# mezzanine.net
KiCad netlist of a schematic drawn in Altium Designer
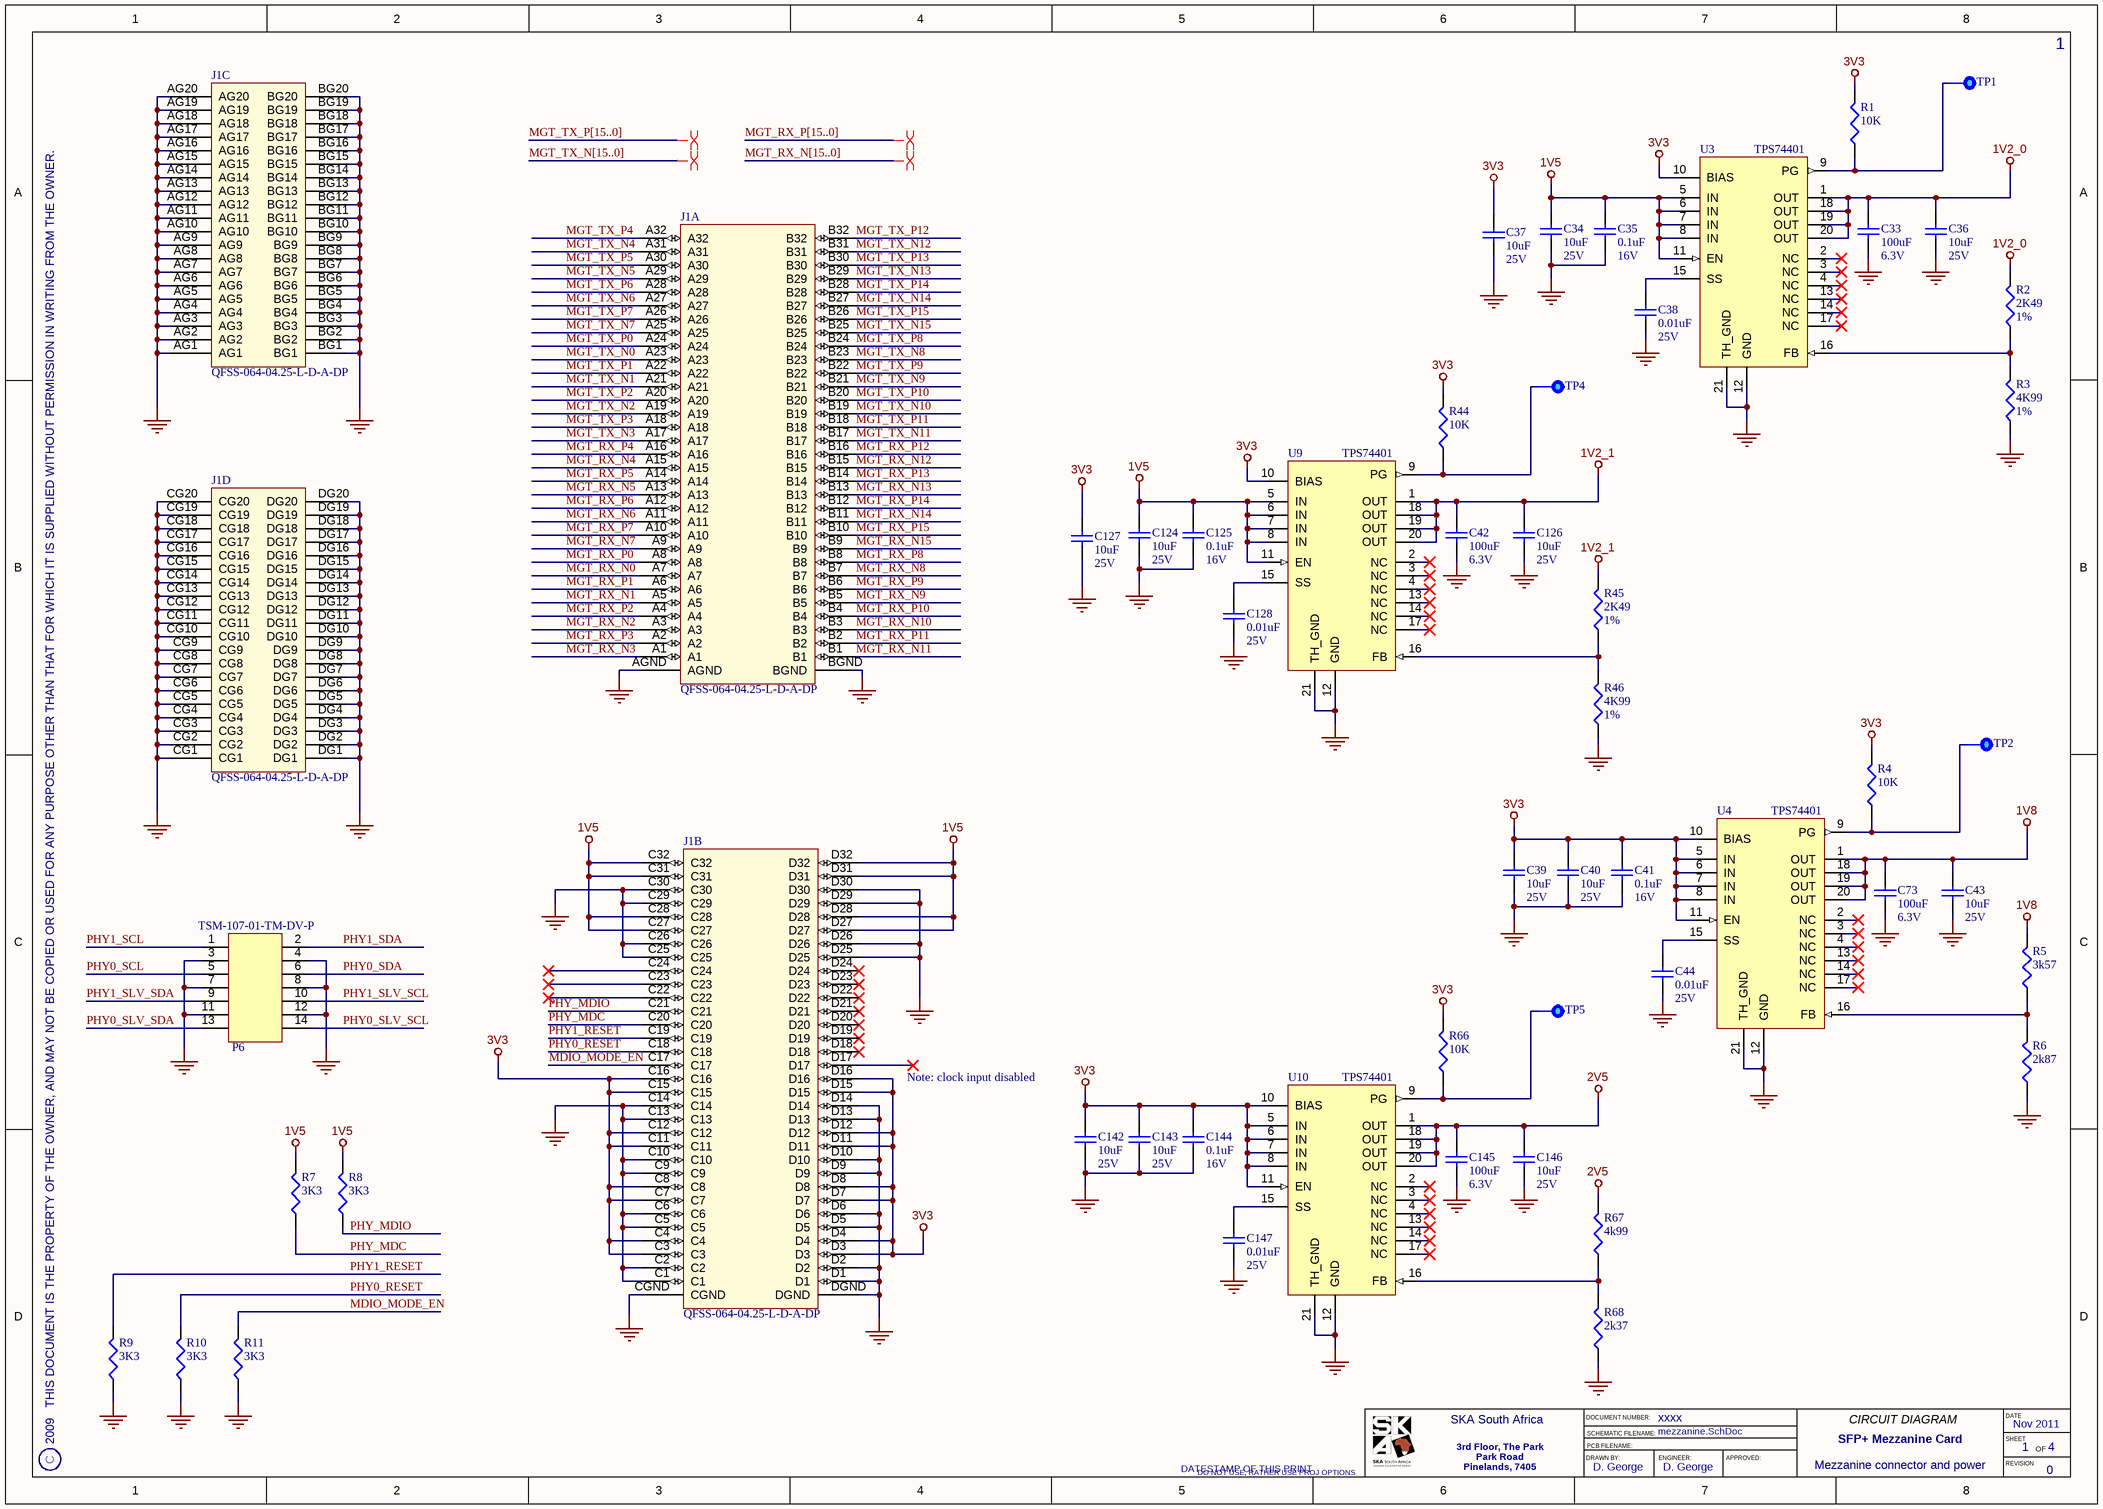
[diagram p0: mezzanine.SchDoc]

(export (version "E")
  (design (tool "Eeschema 10.0.6"))
  (components
    (comp (ref "C33")
      (value "100uF")
      (footprint "CAPC3225X270L")
      (description "100uF, 1210, Ceramic Capacitor")
      (fields
        (field (name "RATING") "6.3V")
        (field (name "MANUFACTURER") "TDK")
        (field (name "PARTNUM") "C3225X5R0J107M")
      )
      (libsource (lib "altium_db") (part "CapStd"))
    )
    (comp (ref "C34")
      (value "10uF")
      (footprint "CAPC3225X200L")
      (description "10uF, Ceramic Capacitor")
      (fields
        (field (name "RATING") "25V")
        (field (name "MANUFACTURER") "MURATA")
        (field (name "PARTNUM") "GRM32DR61E106KA12L")
      )
      (libsource (lib "altium_db") (part "CapStd"))
    )
    (comp (ref "C35")
      (value "0.1uF")
      (footprint "CAPC1005X60L")
      (description "0.1uF, Ceramic Capacitor")
      (fields
        (field (name "RATING") "16V")
        (field (name "MANUFACTURER") "VENKEL")
        (field (name "PARTNUM") "C0402X7R160-104KN")
      )
      (libsource (lib "altium_db") (part "CapStd"))
    )
    (comp (ref "C36")
      (value "10uF")
      (footprint "CAPC3225X200L")
      (description "10uF, Ceramic Capacitor")
      (fields
        (field (name "RATING") "25V")
        (field (name "MANUFACTURER") "MURATA")
        (field (name "PARTNUM") "GRM32DR61E106KA12L")
      )
      (libsource (lib "altium_db") (part "CapStd"))
    )
    (comp (ref "C37")
      (value "10uF")
      (footprint "CAPC3225X200L")
      (description "10uF, Ceramic Capacitor")
      (fields
        (field (name "RATING") "25V")
        (field (name "MANUFACTURER") "MURATA")
        (field (name "PARTNUM") "GRM32DR61E106KA12L")
      )
      (libsource (lib "altium_db") (part "CapStd"))
    )
    (comp (ref "C38")
      (value "0.01uF")
      (footprint "CAPC1005X55L")
      (description "0.01uF, Ceramic Capacitor")
      (fields
        (field (name "RATING") "25V")
        (field (name "MANUFACTURER") "MURATA")
        (field (name "PARTNUM") "GRM155R71E103KA01D")
      )
      (libsource (lib "altium_db") (part "CapStd"))
    )
    (comp (ref "C39")
      (value "10uF")
      (footprint "CAPC3225X200L")
      (description "10uF, Ceramic Capacitor")
      (fields
        (field (name "RATING") "25V")
        (field (name "MANUFACTURER") "MURATA")
        (field (name "PARTNUM") "GRM32DR61E106KA12L")
      )
      (libsource (lib "altium_db") (part "CapStd"))
    )
    (comp (ref "C40")
      (value "10uF")
      (footprint "CAPC3225X200L")
      (description "10uF, Ceramic Capacitor")
      (fields
        (field (name "RATING") "25V")
        (field (name "MANUFACTURER") "MURATA")
        (field (name "PARTNUM") "GRM32DR61E106KA12L")
      )
      (libsource (lib "altium_db") (part "CapStd"))
    )
    (comp (ref "C41")
      (value "0.1uF")
      (footprint "CAPC1005X60L")
      (description "0.1uF, Ceramic Capacitor")
      (fields
        (field (name "RATING") "16V")
        (field (name "MANUFACTURER") "VENKEL")
        (field (name "PARTNUM") "C0402X7R160-104KN")
      )
      (libsource (lib "altium_db") (part "CapStd"))
    )
    (comp (ref "C42")
      (value "100uF")
      (footprint "CAPC3225X270L")
      (description "100uF, 1210, Ceramic Capacitor")
      (fields
        (field (name "RATING") "6.3V")
        (field (name "MANUFACTURER") "TDK")
        (field (name "PARTNUM") "C3225X5R0J107M")
      )
      (libsource (lib "altium_db") (part "CapStd"))
    )
    (comp (ref "C43")
      (value "10uF")
      (footprint "CAPC3225X200L")
      (description "10uF, Ceramic Capacitor")
      (fields
        (field (name "RATING") "25V")
        (field (name "MANUFACTURER") "MURATA")
        (field (name "PARTNUM") "GRM32DR61E106KA12L")
      )
      (libsource (lib "altium_db") (part "CapStd"))
    )
    (comp (ref "C44")
      (value "0.01uF")
      (footprint "CAPC1005X55L")
      (description "0.01uF, Ceramic Capacitor")
      (fields
        (field (name "RATING") "25V")
        (field (name "MANUFACTURER") "MURATA")
        (field (name "PARTNUM") "GRM155R71E103KA01D")
      )
      (libsource (lib "altium_db") (part "CapStd"))
    )
    (comp (ref "C73")
      (value "100uF")
      (footprint "CAPC3225X270L")
      (description "100uF, 1210, Ceramic Capacitor")
      (fields
        (field (name "RATING") "6.3V")
        (field (name "MANUFACTURER") "TDK")
        (field (name "PARTNUM") "C3225X5R0J107M")
      )
      (libsource (lib "altium_db") (part "CapStd"))
    )
    (comp (ref "C124")
      (value "10uF")
      (footprint "CAPC3225X200L")
      (description "10uF, Ceramic Capacitor")
      (fields
        (field (name "RATING") "25V")
        (field (name "MANUFACTURER") "MURATA")
        (field (name "PARTNUM") "GRM32DR61E106KA12L")
      )
      (libsource (lib "altium_db") (part "CapStd"))
    )
    (comp (ref "C125")
      (value "0.1uF")
      (footprint "CAPC1005X60L")
      (description "0.1uF, Ceramic Capacitor")
      (fields
        (field (name "RATING") "16V")
        (field (name "MANUFACTURER") "VENKEL")
        (field (name "PARTNUM") "C0402X7R160-104KN")
      )
      (libsource (lib "altium_db") (part "CapStd"))
    )
    (comp (ref "C126")
      (value "10uF")
      (footprint "CAPC3225X200L")
      (description "10uF, Ceramic Capacitor")
      (fields
        (field (name "RATING") "25V")
        (field (name "MANUFACTURER") "MURATA")
        (field (name "PARTNUM") "GRM32DR61E106KA12L")
      )
      (libsource (lib "altium_db") (part "CapStd"))
    )
    (comp (ref "C127")
      (value "10uF")
      (footprint "CAPC3225X200L")
      (description "10uF, Ceramic Capacitor")
      (fields
        (field (name "RATING") "25V")
        (field (name "MANUFACTURER") "MURATA")
        (field (name "PARTNUM") "GRM32DR61E106KA12L")
      )
      (libsource (lib "altium_db") (part "CapStd"))
    )
    (comp (ref "C128")
      (value "0.01uF")
      (footprint "CAPC1005X55L")
      (description "0.01uF, Ceramic Capacitor")
      (fields
        (field (name "RATING") "25V")
        (field (name "MANUFACTURER") "MURATA")
        (field (name "PARTNUM") "GRM155R71E103KA01D")
      )
      (libsource (lib "altium_db") (part "CapStd"))
    )
    (comp (ref "C142")
      (value "10uF")
      (footprint "CAPC3225X200L")
      (description "10uF, Ceramic Capacitor")
      (fields
        (field (name "RATING") "25V")
        (field (name "MANUFACTURER") "MURATA")
        (field (name "PARTNUM") "GRM32DR61E106KA12L")
      )
      (libsource (lib "altium_db") (part "CapStd"))
    )
    (comp (ref "C143")
      (value "10uF")
      (footprint "CAPC3225X200L")
      (description "10uF, Ceramic Capacitor")
      (fields
        (field (name "RATING") "25V")
        (field (name "MANUFACTURER") "MURATA")
        (field (name "PARTNUM") "GRM32DR61E106KA12L")
      )
      (libsource (lib "altium_db") (part "CapStd"))
    )
    (comp (ref "C144")
      (value "0.1uF")
      (footprint "CAPC1005X60L")
      (description "0.1uF, Ceramic Capacitor")
      (fields
        (field (name "RATING") "16V")
        (field (name "MANUFACTURER") "VENKEL")
        (field (name "PARTNUM") "C0402X7R160-104KN")
      )
      (libsource (lib "altium_db") (part "CapStd"))
    )
    (comp (ref "C145")
      (value "100uF")
      (footprint "CAPC3225X270L")
      (description "100uF, 1210, Ceramic Capacitor")
      (fields
        (field (name "RATING") "6.3V")
        (field (name "MANUFACTURER") "TDK")
        (field (name "PARTNUM") "C3225X5R0J107M")
      )
      (libsource (lib "altium_db") (part "CapStd"))
    )
    (comp (ref "C146")
      (value "10uF")
      (footprint "CAPC3225X200L")
      (description "10uF, Ceramic Capacitor")
      (fields
        (field (name "RATING") "25V")
        (field (name "MANUFACTURER") "MURATA")
        (field (name "PARTNUM") "GRM32DR61E106KA12L")
      )
      (libsource (lib "altium_db") (part "CapStd"))
    )
    (comp (ref "C147")
      (value "0.01uF")
      (footprint "CAPC1005X55L")
      (description "0.01uF, Ceramic Capacitor")
      (fields
        (field (name "RATING") "25V")
        (field (name "MANUFACTURER") "MURATA")
        (field (name "PARTNUM") "GRM155R71E103KA01D")
      )
      (libsource (lib "altium_db") (part "CapStd"))
    )
    (comp (ref "J1")
      (value "QFSS-064-04.25-L-D-A-DP")
      (footprint "SAMTEC_QFSS-064-04.25-L-D-DP-A")
      (description "Shielded, 64-Differential Pair, Rugged High-Speed Terminal Strip, 0.635mm Pitch")
      (fields (field (name "PARTNUM") "QFSS-064-04.25-L-D-A-DP") (field (name "MANUFACTURER") "SAMTEC"))
      (libsource (lib "") (part "QFSS-064-04.25-L-D-A-DP_1"))
    )
    (comp (ref "P6")
      (value "TSM-107-01-TM-DV-P")
      (footprint "SAMTEC_TSM-107-01-TM-DV-P")
      (description "2x7, 2.54 mm Pitch, Male Header")
      (fields (field (name "PARTNUM") "TSM-107-01-TM-DV-P") (field (name "MANUFACTURER") "SAMTEC"))
      (libsource (lib "altium_db") (part "con_hdr_2x7"))
    )
    (comp (ref "R1")
      (value "10K")
      (footprint "RESC1005X40L")
      (description "10K, 1.1mm x 0.5mm, Thick Film Resistor")
      (fields (field (name "MANUFACTURER") "ROYALOHM") (field (name "PARTNUM") "0402WGJ0103T1E"))
      (libsource (lib "altium_db") (part "ResStd"))
    )
    (comp (ref "R2")
      (value "2K49")
      (footprint "RESC1005X40L")
      (description "2K49, 1.1mm x 0.5mm, Thick Film Resistor")
      (fields
        (field (name "MANUFACTURER") "ROYALOHM")
        (field (name "PARTNUM") "0402WGF2K49T1E")
        (field (name "TOLERANCE") "1%")
      )
      (libsource (lib "altium_db") (part "ResStd"))
    )
    (comp (ref "R3")
      (value "4K99")
      (footprint "RESC1005X40L")
      (description "4K99, 1.1mm x 0.5mm, Thick Film Resistor")
      (fields
        (field (name "MANUFACTURER") "ROYALOHM")
        (field (name "PARTNUM") "0402WGF4991T1E")
        (field (name "TOLERANCE") "1%")
      )
      (libsource (lib "altium_db") (part "ResStd"))
    )
    (comp (ref "R4")
      (value "10K")
      (footprint "RESC1005X40L")
      (description "10K, 1.1mm x 0.5mm, Thick Film Resistor")
      (fields (field (name "MANUFACTURER") "ROYALOHM") (field (name "PARTNUM") "0402WGJ0103T1E"))
      (libsource (lib "altium_db") (part "ResStd"))
    )
    (comp (ref "R5")
      (value "3k57")
      (footprint "RESC1005X40L")
      (description "3K57, 1.1mm x 0.5mm, Thick Film Resistor")
      (fields (field (name "MANUFACTURER") "STACKPOLE") (field (name "PARTNUM") "RMC0402FT3K57"))
      (libsource (lib "altium_db") (part "ResStd"))
    )
    (comp (ref "R6")
      (value "2k87")
      (footprint "RESC1005X40L")
      (description "2K87, 1.1mm x 0.5mm, Thick Film Resistor")
      (fields (field (name "MANUFACTURER") "STACKPOLE") (field (name "PARTNUM") "RMC0402FT2K87"))
      (libsource (lib "altium_db") (part "ResStd"))
    )
    (comp (ref "R7")
      (value "3K3")
      (footprint "RESC1005X40L")
      (description "3K3, 1.1mm x 0.5mm, Thick Film Resistor")
      (fields (field (name "MANUFACTURER") "ROYALOHM") (field (name "PARTNUM") "0402WGJ0332T1E"))
      (libsource (lib "altium_db") (part "ResStd"))
    )
    (comp (ref "R8")
      (value "3K3")
      (footprint "RESC1005X40L")
      (description "3K3, 1.1mm x 0.5mm, Thick Film Resistor")
      (fields (field (name "MANUFACTURER") "ROYALOHM") (field (name "PARTNUM") "0402WGJ0332T1E"))
      (libsource (lib "altium_db") (part "ResStd"))
    )
    (comp (ref "R9")
      (value "3K3")
      (footprint "RESC1005X40L")
      (description "3K3, 1.1mm x 0.5mm, Thick Film Resistor")
      (fields (field (name "MANUFACTURER") "ROYALOHM") (field (name "PARTNUM") "0402WGJ0332T1E"))
      (libsource (lib "altium_db") (part "ResStd"))
    )
    (comp (ref "R10")
      (value "3K3")
      (footprint "RESC1005X40L")
      (description "3K3, 1.1mm x 0.5mm, Thick Film Resistor")
      (fields (field (name "MANUFACTURER") "ROYALOHM") (field (name "PARTNUM") "0402WGJ0332T1E"))
      (libsource (lib "altium_db") (part "ResStd"))
    )
    (comp (ref "R11")
      (value "3K3")
      (footprint "RESC1005X40L")
      (description "3K3, 1.1mm x 0.5mm, Thick Film Resistor")
      (fields (field (name "MANUFACTURER") "ROYALOHM") (field (name "PARTNUM") "0402WGJ0332T1E"))
      (libsource (lib "altium_db") (part "ResStd"))
    )
    (comp (ref "R44")
      (value "10K")
      (footprint "RESC1005X40L")
      (description "10K, 1.1mm x 0.5mm, Thick Film Resistor")
      (fields (field (name "MANUFACTURER") "ROYALOHM") (field (name "PARTNUM") "0402WGJ0103T1E"))
      (libsource (lib "altium_db") (part "ResStd"))
    )
    (comp (ref "R45")
      (value "2K49")
      (footprint "RESC1005X40L")
      (description "2K49, 1.1mm x 0.5mm, Thick Film Resistor")
      (fields
        (field (name "MANUFACTURER") "ROYALOHM")
        (field (name "PARTNUM") "0402WGF2K49T1E")
        (field (name "TOLERANCE") "1%")
      )
      (libsource (lib "altium_db") (part "ResStd"))
    )
    (comp (ref "R46")
      (value "4K99")
      (footprint "RESC1005X40L")
      (description "4K99, 1.1mm x 0.5mm, Thick Film Resistor")
      (fields
        (field (name "MANUFACTURER") "ROYALOHM")
        (field (name "PARTNUM") "0402WGF4991T1E")
        (field (name "TOLERANCE") "1%")
      )
      (libsource (lib "altium_db") (part "ResStd"))
    )
    (comp (ref "R66")
      (value "10K")
      (footprint "RESC1005X40L")
      (description "10K, 1.1mm x 0.5mm, Thick Film Resistor")
      (fields (field (name "MANUFACTURER") "ROYALOHM") (field (name "PARTNUM") "0402WGJ0103T1E"))
      (libsource (lib "altium_db") (part "ResStd"))
    )
    (comp (ref "R67")
      (value "4k99")
      (footprint "RESC1005X40L")
      (description "3K57, 1.1mm x 0.5mm, Thick Film Resistor")
      (fields (field (name "MANUFACTURER") "STACKPOLE") (field (name "PARTNUM") "RMC0402FT3K57"))
      (libsource (lib "altium_db") (part "ResStd"))
    )
    (comp (ref "R68")
      (value "2k37")
      (footprint "RESC1005X40L")
      (description "2K87, 1.1mm x 0.5mm, Thick Film Resistor")
      (fields (field (name "MANUFACTURER") "STACKPOLE") (field (name "PARTNUM") "RMC0402FT2K87"))
      (libsource (lib "altium_db") (part "ResStd"))
    )
    (comp (ref "TP1")
      (value "Testpoint")
      (footprint "TP100")
      (description "1mm Diameter, through-hole, Circular Test-point")
      (libsource (lib "altium_db") (part "Testpoint"))
    )
    (comp (ref "TP2")
      (value "Testpoint")
      (footprint "TP100")
      (description "1mm Diameter, through-hole, Circular Test-point")
      (libsource (lib "altium_db") (part "Testpoint"))
    )
    (comp (ref "TP4")
      (value "Testpoint")
      (footprint "TP100")
      (description "1mm Diameter, through-hole, Circular Test-point")
      (libsource (lib "altium_db") (part "Testpoint"))
    )
    (comp (ref "TP5")
      (value "Testpoint")
      (footprint "TP100")
      (description "1mm Diameter, through-hole, Circular Test-point")
      (libsource (lib "altium_db") (part "Testpoint"))
    )
    (comp (ref "U3")
      (value "TPS74401")
      (footprint "VQFN20")
      (description "3.0A Ultra-LDO with Programmable Soft-Start")
      (fields (field (name "MANUFACTURER") "Texas Instruments"))
      (libsource (lib "altium_db") (part "TPS74401"))
    )
    (comp (ref "U4")
      (value "TPS74401")
      (footprint "VQFN20")
      (description "3.0A Ultra-LDO with Programmable Soft-Start")
      (fields (field (name "MANUFACTURER") "Texas Instruments"))
      (libsource (lib "altium_db") (part "TPS74401"))
    )
    (comp (ref "U9")
      (value "TPS74401")
      (footprint "VQFN20")
      (description "3.0A Ultra-LDO with Programmable Soft-Start")
      (fields (field (name "MANUFACTURER") "Texas Instruments"))
      (libsource (lib "altium_db") (part "TPS74401"))
    )
    (comp (ref "U10")
      (value "TPS74401")
      (footprint "VQFN20")
      (description "3.0A Ultra-LDO with Programmable Soft-Start")
      (fields (field (name "MANUFACTURER") "Texas Instruments"))
      (libsource (lib "altium_db") (part "TPS74401"))
    )
  )
  (nets
    (net (code "1") (name "/MDIO_MODE_EN") (class "Default")
      (node (ref "J1") (pin "C17") (pinfunction "C17_C17") (pintype "bidirectional"))
      (node (ref "R11") (pin "2") (pinfunction "2_2") (pintype "passive"))
    )
    (net (code "2") (name "/MGT_RX_N0") (class "Default")
      (node (ref "J1") (pin "A7") (pinfunction "A7_A7") (pintype "bidirectional"))
    )
    (net (code "3") (name "/MGT_RX_N1") (class "Default")
      (node (ref "J1") (pin "A5") (pinfunction "A5_A5") (pintype "bidirectional"))
    )
    (net (code "4") (name "/MGT_RX_N2") (class "Default")
      (node (ref "J1") (pin "A3") (pinfunction "A3_A3") (pintype "bidirectional"))
    )
    (net (code "5") (name "/MGT_RX_N3") (class "Default")
      (node (ref "J1") (pin "A1") (pinfunction "A1_A1") (pintype "bidirectional"))
    )
    (net (code "6") (name "/MGT_RX_N4") (class "Default")
      (node (ref "J1") (pin "A15") (pinfunction "A15_A15") (pintype "bidirectional"))
    )
    (net (code "7") (name "/MGT_RX_N5") (class "Default")
      (node (ref "J1") (pin "A13") (pinfunction "A13_A13") (pintype "bidirectional"))
    )
    (net (code "8") (name "/MGT_RX_N6") (class "Default")
      (node (ref "J1") (pin "A11") (pinfunction "A11_A11") (pintype "bidirectional"))
    )
    (net (code "9") (name "/MGT_RX_N7") (class "Default")
      (node (ref "J1") (pin "A9") (pinfunction "A9_A9") (pintype "bidirectional"))
    )
    (net (code "10") (name "/MGT_RX_N8") (class "Default")
      (node (ref "J1") (pin "B7") (pinfunction "B7_B7") (pintype "bidirectional"))
    )
    (net (code "11") (name "/MGT_RX_N9") (class "Default")
      (node (ref "J1") (pin "B5") (pinfunction "B5_B5") (pintype "bidirectional"))
    )
    (net (code "12") (name "/MGT_RX_N10") (class "Default")
      (node (ref "J1") (pin "B3") (pinfunction "B3_B3") (pintype "bidirectional"))
    )
    (net (code "13") (name "/MGT_RX_N11") (class "Default")
      (node (ref "J1") (pin "B1") (pinfunction "B1_B1") (pintype "bidirectional"))
    )
    (net (code "14") (name "/MGT_RX_N12") (class "Default")
      (node (ref "J1") (pin "B15") (pinfunction "B15_B15") (pintype "bidirectional"))
    )
    (net (code "15") (name "/MGT_RX_N13") (class "Default")
      (node (ref "J1") (pin "B13") (pinfunction "B13_B13") (pintype "bidirectional"))
    )
    (net (code "16") (name "/MGT_RX_N14") (class "Default")
      (node (ref "J1") (pin "B11") (pinfunction "B11_B11") (pintype "bidirectional"))
    )
    (net (code "17") (name "/MGT_RX_N15") (class "Default")
      (node (ref "J1") (pin "B9") (pinfunction "B9_B9") (pintype "bidirectional"))
    )
    (net (code "19") (name "/MGT_RX_P0") (class "Default")
      (node (ref "J1") (pin "A8") (pinfunction "A8_A8") (pintype "bidirectional"))
    )
    (net (code "20") (name "/MGT_RX_P1") (class "Default")
      (node (ref "J1") (pin "A6") (pinfunction "A6_A6") (pintype "bidirectional"))
    )
    (net (code "21") (name "/MGT_RX_P2") (class "Default")
      (node (ref "J1") (pin "A4") (pinfunction "A4_A4") (pintype "bidirectional"))
    )
    (net (code "22") (name "/MGT_RX_P3") (class "Default")
      (node (ref "J1") (pin "A2") (pinfunction "A2_A2") (pintype "bidirectional"))
    )
    (net (code "23") (name "/MGT_RX_P4") (class "Default")
      (node (ref "J1") (pin "A16") (pinfunction "A16_A16") (pintype "bidirectional"))
    )
    (net (code "24") (name "/MGT_RX_P5") (class "Default")
      (node (ref "J1") (pin "A14") (pinfunction "A14_A14") (pintype "bidirectional"))
    )
    (net (code "25") (name "/MGT_RX_P6") (class "Default")
      (node (ref "J1") (pin "A12") (pinfunction "A12_A12") (pintype "bidirectional"))
    )
    (net (code "26") (name "/MGT_RX_P7") (class "Default")
      (node (ref "J1") (pin "A10") (pinfunction "A10_A10") (pintype "bidirectional"))
    )
    (net (code "27") (name "/MGT_RX_P8") (class "Default")
      (node (ref "J1") (pin "B8") (pinfunction "B8_B8") (pintype "bidirectional"))
    )
    (net (code "28") (name "/MGT_RX_P9") (class "Default")
      (node (ref "J1") (pin "B6") (pinfunction "B6_B6") (pintype "bidirectional"))
    )
    (net (code "29") (name "/MGT_RX_P10") (class "Default")
      (node (ref "J1") (pin "B4") (pinfunction "B4_B4") (pintype "bidirectional"))
    )
    (net (code "30") (name "/MGT_RX_P11") (class "Default")
      (node (ref "J1") (pin "B2") (pinfunction "B2_B2") (pintype "bidirectional"))
    )
    (net (code "31") (name "/MGT_RX_P12") (class "Default")
      (node (ref "J1") (pin "B16") (pinfunction "B16_B16") (pintype "bidirectional"))
    )
    (net (code "32") (name "/MGT_RX_P13") (class "Default")
      (node (ref "J1") (pin "B14") (pinfunction "B14_B14") (pintype "bidirectional"))
    )
    (net (code "33") (name "/MGT_RX_P14") (class "Default")
      (node (ref "J1") (pin "B12") (pinfunction "B12_B12") (pintype "bidirectional"))
    )
    (net (code "34") (name "/MGT_RX_P15") (class "Default")
      (node (ref "J1") (pin "B10") (pinfunction "B10_B10") (pintype "bidirectional"))
    )
    (net (code "36") (name "/MGT_TX_N0") (class "Default")
      (node (ref "J1") (pin "A23") (pinfunction "A23_A23") (pintype "bidirectional"))
    )
    (net (code "37") (name "/MGT_TX_N1") (class "Default")
      (node (ref "J1") (pin "A21") (pinfunction "A21_A21") (pintype "bidirectional"))
    )
    (net (code "38") (name "/MGT_TX_N2") (class "Default")
      (node (ref "J1") (pin "A19") (pinfunction "A19_A19") (pintype "bidirectional"))
    )
    (net (code "39") (name "/MGT_TX_N3") (class "Default")
      (node (ref "J1") (pin "A17") (pinfunction "A17_A17") (pintype "bidirectional"))
    )
    (net (code "40") (name "/MGT_TX_N4") (class "Default")
      (node (ref "J1") (pin "A31") (pinfunction "A31_A31") (pintype "bidirectional"))
    )
    (net (code "41") (name "/MGT_TX_N5") (class "Default")
      (node (ref "J1") (pin "A29") (pinfunction "A29_A29") (pintype "bidirectional"))
    )
    (net (code "42") (name "/MGT_TX_N6") (class "Default")
      (node (ref "J1") (pin "A27") (pinfunction "A27_A27") (pintype "bidirectional"))
    )
    (net (code "43") (name "/MGT_TX_N7") (class "Default")
      (node (ref "J1") (pin "A25") (pinfunction "A25_A25") (pintype "bidirectional"))
    )
    (net (code "44") (name "/MGT_TX_N8") (class "Default")
      (node (ref "J1") (pin "B23") (pinfunction "B23_B23") (pintype "bidirectional"))
    )
    (net (code "45") (name "/MGT_TX_N9") (class "Default")
      (node (ref "J1") (pin "B21") (pinfunction "B21_B21") (pintype "bidirectional"))
    )
    (net (code "46") (name "/MGT_TX_N10") (class "Default")
      (node (ref "J1") (pin "B19") (pinfunction "B19_B19") (pintype "bidirectional"))
    )
    (net (code "47") (name "/MGT_TX_N11") (class "Default")
      (node (ref "J1") (pin "B17") (pinfunction "B17_B17") (pintype "bidirectional"))
    )
    (net (code "48") (name "/MGT_TX_N12") (class "Default")
      (node (ref "J1") (pin "B31") (pinfunction "B31_B31") (pintype "bidirectional"))
    )
    (net (code "49") (name "/MGT_TX_N13") (class "Default")
      (node (ref "J1") (pin "B29") (pinfunction "B29_B29") (pintype "bidirectional"))
    )
    (net (code "50") (name "/MGT_TX_N14") (class "Default")
      (node (ref "J1") (pin "B27") (pinfunction "B27_B27") (pintype "bidirectional"))
    )
    (net (code "51") (name "/MGT_TX_N15") (class "Default")
      (node (ref "J1") (pin "B25") (pinfunction "B25_B25") (pintype "bidirectional"))
    )
    (net (code "53") (name "/MGT_TX_P0") (class "Default")
      (node (ref "J1") (pin "A24") (pinfunction "A24_A24") (pintype "bidirectional"))
    )
    (net (code "54") (name "/MGT_TX_P1") (class "Default")
      (node (ref "J1") (pin "A22") (pinfunction "A22_A22") (pintype "bidirectional"))
    )
    (net (code "55") (name "/MGT_TX_P2") (class "Default")
      (node (ref "J1") (pin "A20") (pinfunction "A20_A20") (pintype "bidirectional"))
    )
    (net (code "56") (name "/MGT_TX_P3") (class "Default")
      (node (ref "J1") (pin "A18") (pinfunction "A18_A18") (pintype "bidirectional"))
    )
    (net (code "57") (name "/MGT_TX_P4") (class "Default")
      (node (ref "J1") (pin "A32") (pinfunction "A32_A32") (pintype "bidirectional"))
    )
    (net (code "58") (name "/MGT_TX_P5") (class "Default")
      (node (ref "J1") (pin "A30") (pinfunction "A30_A30") (pintype "bidirectional"))
    )
    (net (code "59") (name "/MGT_TX_P6") (class "Default")
      (node (ref "J1") (pin "A28") (pinfunction "A28_A28") (pintype "bidirectional"))
    )
    (net (code "60") (name "/MGT_TX_P7") (class "Default")
      (node (ref "J1") (pin "A26") (pinfunction "A26_A26") (pintype "bidirectional"))
    )
    (net (code "61") (name "/MGT_TX_P8") (class "Default")
      (node (ref "J1") (pin "B24") (pinfunction "B24_B24") (pintype "bidirectional"))
    )
    (net (code "62") (name "/MGT_TX_P9") (class "Default")
      (node (ref "J1") (pin "B22") (pinfunction "B22_B22") (pintype "bidirectional"))
    )
    (net (code "63") (name "/MGT_TX_P10") (class "Default")
      (node (ref "J1") (pin "B20") (pinfunction "B20_B20") (pintype "bidirectional"))
    )
    (net (code "64") (name "/MGT_TX_P11") (class "Default")
      (node (ref "J1") (pin "B18") (pinfunction "B18_B18") (pintype "bidirectional"))
    )
    (net (code "65") (name "/MGT_TX_P12") (class "Default")
      (node (ref "J1") (pin "B32") (pinfunction "B32_B32") (pintype "bidirectional"))
    )
    (net (code "66") (name "/MGT_TX_P13") (class "Default")
      (node (ref "J1") (pin "B30") (pinfunction "B30_B30") (pintype "bidirectional"))
    )
    (net (code "67") (name "/MGT_TX_P14") (class "Default")
      (node (ref "J1") (pin "B28") (pinfunction "B28_B28") (pintype "bidirectional"))
    )
    (net (code "68") (name "/MGT_TX_P15") (class "Default")
      (node (ref "J1") (pin "B26") (pinfunction "B26_B26") (pintype "bidirectional"))
    )
    (net (code "70") (name "/PHY0_RESET") (class "Default")
      (node (ref "J1") (pin "C18") (pinfunction "C18_C18") (pintype "bidirectional"))
      (node (ref "R10") (pin "2") (pinfunction "2_2") (pintype "passive"))
    )
    (net (code "71") (name "/PHY0_SCL") (class "Default")
      (node (ref "P6") (pin "5") (pinfunction "5_5") (pintype "passive"))
    )
    (net (code "72") (name "/PHY0_SDA") (class "Default")
      (node (ref "P6") (pin "6") (pinfunction "6_6") (pintype "passive"))
    )
    (net (code "73") (name "/PHY0_SLV_SCL") (class "Default")
      (node (ref "P6") (pin "14") (pinfunction "14_14") (pintype "passive"))
    )
    (net (code "74") (name "/PHY0_SLV_SDA") (class "Default")
      (node (ref "P6") (pin "13") (pinfunction "13_13") (pintype "passive"))
    )
    (net (code "75") (name "/PHY1_RESET") (class "Default")
      (node (ref "J1") (pin "C19") (pinfunction "C19_C19") (pintype "bidirectional"))
      (node (ref "R9") (pin "2") (pinfunction "2_2") (pintype "passive"))
    )
    (net (code "76") (name "/PHY1_SCL") (class "Default")
      (node (ref "P6") (pin "1") (pinfunction "1_1") (pintype "passive"))
    )
    (net (code "77") (name "/PHY1_SDA") (class "Default")
      (node (ref "P6") (pin "2") (pinfunction "2_2") (pintype "passive"))
    )
    (net (code "78") (name "/PHY1_SLV_SCL") (class "Default")
      (node (ref "P6") (pin "10") (pinfunction "10_10") (pintype "passive"))
    )
    (net (code "79") (name "/PHY1_SLV_SDA") (class "Default")
      (node (ref "P6") (pin "9") (pinfunction "9_9") (pintype "passive"))
    )
    (net (code "80") (name "/PHY_MDC") (class "Default")
      (node (ref "J1") (pin "C20") (pinfunction "C20_C20") (pintype "bidirectional"))
      (node (ref "R7") (pin "1") (pinfunction "1_1") (pintype "passive"))
    )
    (net (code "81") (name "/PHY_MDIO") (class "Default")
      (node (ref "J1") (pin "C21") (pinfunction "C21_C21") (pintype "bidirectional"))
      (node (ref "R8") (pin "1") (pinfunction "1_1") (pintype "passive"))
    )
    (net (code "82") (name "1V2_0") (class "Default")
      (node (ref "C33") (pin "2") (pinfunction "2_2") (pintype "passive"))
      (node (ref "C36") (pin "2") (pinfunction "2_2") (pintype "passive"))
      (node (ref "R2") (pin "2") (pinfunction "2_2") (pintype "passive"))
      (node (ref "U3") (pin "1") (pinfunction "OUT_1") (pintype "power_in"))
      (node (ref "U3") (pin "18") (pinfunction "OUT_18") (pintype "power_in"))
      (node (ref "U3") (pin "19") (pinfunction "OUT_19") (pintype "power_in"))
      (node (ref "U3") (pin "20") (pinfunction "OUT_20") (pintype "power_in"))
    )
    (net (code "83") (name "1V2_1") (class "Default")
      (node (ref "C126") (pin "2") (pinfunction "2_2") (pintype "passive"))
      (node (ref "C42") (pin "2") (pinfunction "2_2") (pintype "passive"))
      (node (ref "R45") (pin "2") (pinfunction "2_2") (pintype "passive"))
      (node (ref "U9") (pin "1") (pinfunction "OUT_1") (pintype "power_in"))
      (node (ref "U9") (pin "18") (pinfunction "OUT_18") (pintype "power_in"))
      (node (ref "U9") (pin "19") (pinfunction "OUT_19") (pintype "power_in"))
      (node (ref "U9") (pin "20") (pinfunction "OUT_20") (pintype "power_in"))
    )
    (net (code "84") (name "1V5") (class "Default")
      (node (ref "C124") (pin "2") (pinfunction "2_2") (pintype "passive"))
      (node (ref "C125") (pin "2") (pinfunction "2_2") (pintype "passive"))
      (node (ref "C34") (pin "2") (pinfunction "2_2") (pintype "passive"))
      (node (ref "C35") (pin "2") (pinfunction "2_2") (pintype "passive"))
      (node (ref "J1") (pin "C27") (pinfunction "C27_C27") (pintype "bidirectional"))
      (node (ref "J1") (pin "C28") (pinfunction "C28_C28") (pintype "bidirectional"))
      (node (ref "J1") (pin "C31") (pinfunction "C31_C31") (pintype "bidirectional"))
      (node (ref "J1") (pin "C32") (pinfunction "C32_C32") (pintype "bidirectional"))
      (node (ref "J1") (pin "D27") (pinfunction "D27_D27") (pintype "bidirectional"))
      (node (ref "J1") (pin "D28") (pinfunction "D28_D28") (pintype "bidirectional"))
      (node (ref "J1") (pin "D31") (pinfunction "D31_D31") (pintype "bidirectional"))
      (node (ref "J1") (pin "D32") (pinfunction "D32_D32") (pintype "bidirectional"))
      (node (ref "R7") (pin "2") (pinfunction "2_2") (pintype "passive"))
      (node (ref "R8") (pin "2") (pinfunction "2_2") (pintype "passive"))
      (node (ref "U3") (pin "11") (pinfunction "EN_11") (pintype "input"))
      (node (ref "U3") (pin "5") (pinfunction "IN_5") (pintype "power_in"))
      (node (ref "U3") (pin "6") (pinfunction "IN_6") (pintype "power_in"))
      (node (ref "U3") (pin "7") (pinfunction "IN_7") (pintype "power_in"))
      (node (ref "U3") (pin "8") (pinfunction "IN_8") (pintype "power_in"))
      (node (ref "U9") (pin "11") (pinfunction "EN_11") (pintype "input"))
      (node (ref "U9") (pin "5") (pinfunction "IN_5") (pintype "power_in"))
      (node (ref "U9") (pin "6") (pinfunction "IN_6") (pintype "power_in"))
      (node (ref "U9") (pin "7") (pinfunction "IN_7") (pintype "power_in"))
      (node (ref "U9") (pin "8") (pinfunction "IN_8") (pintype "power_in"))
    )
    (net (code "85") (name "1V8") (class "Default")
      (node (ref "C43") (pin "2") (pinfunction "2_2") (pintype "passive"))
      (node (ref "C73") (pin "2") (pinfunction "2_2") (pintype "passive"))
      (node (ref "R5") (pin "2") (pinfunction "2_2") (pintype "passive"))
      (node (ref "U4") (pin "1") (pinfunction "OUT_1") (pintype "power_in"))
      (node (ref "U4") (pin "18") (pinfunction "OUT_18") (pintype "power_in"))
      (node (ref "U4") (pin "19") (pinfunction "OUT_19") (pintype "power_in"))
      (node (ref "U4") (pin "20") (pinfunction "OUT_20") (pintype "power_in"))
    )
    (net (code "86") (name "2V5") (class "Default")
      (node (ref "C145") (pin "2") (pinfunction "2_2") (pintype "passive"))
      (node (ref "C146") (pin "2") (pinfunction "2_2") (pintype "passive"))
      (node (ref "R67") (pin "2") (pinfunction "2_2") (pintype "passive"))
      (node (ref "U10") (pin "1") (pinfunction "OUT_1") (pintype "power_in"))
      (node (ref "U10") (pin "18") (pinfunction "OUT_18") (pintype "power_in"))
      (node (ref "U10") (pin "19") (pinfunction "OUT_19") (pintype "power_in"))
      (node (ref "U10") (pin "20") (pinfunction "OUT_20") (pintype "power_in"))
    )
    (net (code "87") (name "3V3") (class "Default")
      (node (ref "C127") (pin "2") (pinfunction "2_2") (pintype "passive"))
      (node (ref "C142") (pin "2") (pinfunction "2_2") (pintype "passive"))
      (node (ref "C143") (pin "2") (pinfunction "2_2") (pintype "passive"))
      (node (ref "C144") (pin "2") (pinfunction "2_2") (pintype "passive"))
      (node (ref "C37") (pin "2") (pinfunction "2_2") (pintype "passive"))
      (node (ref "C39") (pin "2") (pinfunction "2_2") (pintype "passive"))
      (node (ref "C40") (pin "2") (pinfunction "2_2") (pintype "passive"))
      (node (ref "C41") (pin "2") (pinfunction "2_2") (pintype "passive"))
      (node (ref "J1") (pin "C11") (pinfunction "C11_C11") (pintype "bidirectional"))
      (node (ref "J1") (pin "C12") (pinfunction "C12_C12") (pintype "bidirectional"))
      (node (ref "J1") (pin "C15") (pinfunction "C15_C15") (pintype "bidirectional"))
      (node (ref "J1") (pin "C16") (pinfunction "C16_C16") (pintype "bidirectional"))
      (node (ref "J1") (pin "C3") (pinfunction "C3_C3") (pintype "bidirectional"))
      (node (ref "J1") (pin "C4") (pinfunction "C4_C4") (pintype "bidirectional"))
      (node (ref "J1") (pin "C7") (pinfunction "C7_C7") (pintype "bidirectional"))
      (node (ref "J1") (pin "C8") (pinfunction "C8_C8") (pintype "bidirectional"))
      (node (ref "J1") (pin "D11") (pinfunction "D11_D11") (pintype "bidirectional"))
      (node (ref "J1") (pin "D12") (pinfunction "D12_D12") (pintype "bidirectional"))
      (node (ref "J1") (pin "D15") (pinfunction "D15_D15") (pintype "bidirectional"))
      (node (ref "J1") (pin "D16") (pinfunction "D16_D16") (pintype "bidirectional"))
      (node (ref "J1") (pin "D3") (pinfunction "D3_D3") (pintype "bidirectional"))
      (node (ref "J1") (pin "D4") (pinfunction "D4_D4") (pintype "bidirectional"))
      (node (ref "J1") (pin "D7") (pinfunction "D7_D7") (pintype "bidirectional"))
      (node (ref "J1") (pin "D8") (pinfunction "D8_D8") (pintype "bidirectional"))
      (node (ref "R1") (pin "2") (pinfunction "2_2") (pintype "passive"))
      (node (ref "R4") (pin "2") (pinfunction "2_2") (pintype "passive"))
      (node (ref "R44") (pin "2") (pinfunction "2_2") (pintype "passive"))
      (node (ref "R66") (pin "2") (pinfunction "2_2") (pintype "passive"))
      (node (ref "U10") (pin "10") (pinfunction "BIAS_10") (pintype "power_in"))
      (node (ref "U10") (pin "11") (pinfunction "EN_11") (pintype "input"))
      (node (ref "U10") (pin "5") (pinfunction "IN_5") (pintype "power_in"))
      (node (ref "U10") (pin "6") (pinfunction "IN_6") (pintype "power_in"))
      (node (ref "U10") (pin "7") (pinfunction "IN_7") (pintype "power_in"))
      (node (ref "U10") (pin "8") (pinfunction "IN_8") (pintype "power_in"))
      (node (ref "U3") (pin "10") (pinfunction "BIAS_10") (pintype "power_in"))
      (node (ref "U4") (pin "10") (pinfunction "BIAS_10") (pintype "power_in"))
      (node (ref "U4") (pin "11") (pinfunction "EN_11") (pintype "input"))
      (node (ref "U4") (pin "5") (pinfunction "IN_5") (pintype "power_in"))
      (node (ref "U4") (pin "6") (pinfunction "IN_6") (pintype "power_in"))
      (node (ref "U4") (pin "7") (pinfunction "IN_7") (pintype "power_in"))
      (node (ref "U4") (pin "8") (pinfunction "IN_8") (pintype "power_in"))
      (node (ref "U9") (pin "10") (pinfunction "BIAS_10") (pintype "power_in"))
    )
    (net (code "88") (name "GND") (class "Default")
      (node (ref "C124") (pin "1") (pinfunction "1_1") (pintype "passive"))
      (node (ref "C125") (pin "1") (pinfunction "1_1") (pintype "passive"))
      (node (ref "C126") (pin "1") (pinfunction "1_1") (pintype "passive"))
      (node (ref "C127") (pin "1") (pinfunction "1_1") (pintype "passive"))
      (node (ref "C128") (pin "1") (pinfunction "1_1") (pintype "passive"))
      (node (ref "C142") (pin "1") (pinfunction "1_1") (pintype "passive"))
      (node (ref "C143") (pin "1") (pinfunction "1_1") (pintype "passive"))
      (node (ref "C144") (pin "1") (pinfunction "1_1") (pintype "passive"))
      (node (ref "C145") (pin "1") (pinfunction "1_1") (pintype "passive"))
      (node (ref "C146") (pin "1") (pinfunction "1_1") (pintype "passive"))
      (node (ref "C147") (pin "1") (pinfunction "1_1") (pintype "passive"))
      (node (ref "C33") (pin "1") (pinfunction "1_1") (pintype "passive"))
      (node (ref "C34") (pin "1") (pinfunction "1_1") (pintype "passive"))
      (node (ref "C35") (pin "1") (pinfunction "1_1") (pintype "passive"))
      (node (ref "C36") (pin "1") (pinfunction "1_1") (pintype "passive"))
      (node (ref "C37") (pin "1") (pinfunction "1_1") (pintype "passive"))
      (node (ref "C38") (pin "1") (pinfunction "1_1") (pintype "passive"))
      (node (ref "C39") (pin "1") (pinfunction "1_1") (pintype "passive"))
      (node (ref "C40") (pin "1") (pinfunction "1_1") (pintype "passive"))
      (node (ref "C41") (pin "1") (pinfunction "1_1") (pintype "passive"))
      (node (ref "C42") (pin "1") (pinfunction "1_1") (pintype "passive"))
      (node (ref "C43") (pin "1") (pinfunction "1_1") (pintype "passive"))
      (node (ref "C44") (pin "1") (pinfunction "1_1") (pintype "passive"))
      (node (ref "C73") (pin "1") (pinfunction "1_1") (pintype "passive"))
      (node (ref "J1") (pin "AG1") (pinfunction "AG1_AG1") (pintype "power_in"))
      (node (ref "J1") (pin "AG10") (pinfunction "AG10_AG10") (pintype "power_in"))
      (node (ref "J1") (pin "AG11") (pinfunction "AG11_AG11") (pintype "power_in"))
      (node (ref "J1") (pin "AG12") (pinfunction "AG12_AG12") (pintype "power_in"))
      (node (ref "J1") (pin "AG13") (pinfunction "AG13_AG13") (pintype "power_in"))
      (node (ref "J1") (pin "AG14") (pinfunction "AG14_AG14") (pintype "power_in"))
      (node (ref "J1") (pin "AG15") (pinfunction "AG15_AG15") (pintype "power_in"))
      (node (ref "J1") (pin "AG16") (pinfunction "AG16_AG16") (pintype "power_in"))
      (node (ref "J1") (pin "AG17") (pinfunction "AG17_AG17") (pintype "power_in"))
      (node (ref "J1") (pin "AG18") (pinfunction "AG18_AG18") (pintype "power_in"))
      (node (ref "J1") (pin "AG19") (pinfunction "AG19_AG19") (pintype "power_in"))
      (node (ref "J1") (pin "AG2") (pinfunction "AG2_AG2") (pintype "power_in"))
      (node (ref "J1") (pin "AG20") (pinfunction "AG20_AG20") (pintype "power_in"))
      (node (ref "J1") (pin "AG3") (pinfunction "AG3_AG3") (pintype "power_in"))
      (node (ref "J1") (pin "AG4") (pinfunction "AG4_AG4") (pintype "power_in"))
      (node (ref "J1") (pin "AG5") (pinfunction "AG5_AG5") (pintype "power_in"))
      (node (ref "J1") (pin "AG6") (pinfunction "AG6_AG6") (pintype "power_in"))
      (node (ref "J1") (pin "AG7") (pinfunction "AG7_AG7") (pintype "power_in"))
      (node (ref "J1") (pin "AG8") (pinfunction "AG8_AG8") (pintype "power_in"))
      (node (ref "J1") (pin "AG9") (pinfunction "AG9_AG9") (pintype "power_in"))
      (node (ref "J1") (pin "AGND") (pinfunction "AGND_AGND") (pintype "power_in"))
      (node (ref "J1") (pin "BG1") (pinfunction "BG1_BG1") (pintype "power_in"))
      (node (ref "J1") (pin "BG10") (pinfunction "BG10_BG10") (pintype "power_in"))
      (node (ref "J1") (pin "BG11") (pinfunction "BG11_BG11") (pintype "power_in"))
      (node (ref "J1") (pin "BG12") (pinfunction "BG12_BG12") (pintype "power_in"))
      (node (ref "J1") (pin "BG13") (pinfunction "BG13_BG13") (pintype "power_in"))
      (node (ref "J1") (pin "BG14") (pinfunction "BG14_BG14") (pintype "power_in"))
      (node (ref "J1") (pin "BG15") (pinfunction "BG15_BG15") (pintype "power_in"))
      (node (ref "J1") (pin "BG16") (pinfunction "BG16_BG16") (pintype "power_in"))
      (node (ref "J1") (pin "BG17") (pinfunction "BG17_BG17") (pintype "power_in"))
      (node (ref "J1") (pin "BG18") (pinfunction "BG18_BG18") (pintype "power_in"))
      (node (ref "J1") (pin "BG19") (pinfunction "BG19_BG19") (pintype "power_in"))
      (node (ref "J1") (pin "BG2") (pinfunction "BG2_BG2") (pintype "power_in"))
      (node (ref "J1") (pin "BG20") (pinfunction "BG20_BG20") (pintype "power_in"))
      (node (ref "J1") (pin "BG3") (pinfunction "BG3_BG3") (pintype "power_in"))
      (node (ref "J1") (pin "BG4") (pinfunction "BG4_BG4") (pintype "power_in"))
      (node (ref "J1") (pin "BG5") (pinfunction "BG5_BG5") (pintype "power_in"))
      (node (ref "J1") (pin "BG6") (pinfunction "BG6_BG6") (pintype "power_in"))
      (node (ref "J1") (pin "BG7") (pinfunction "BG7_BG7") (pintype "power_in"))
      (node (ref "J1") (pin "BG8") (pinfunction "BG8_BG8") (pintype "power_in"))
      (node (ref "J1") (pin "BG9") (pinfunction "BG9_BG9") (pintype "power_in"))
      (node (ref "J1") (pin "BGND") (pinfunction "BGND_BGND") (pintype "power_in"))
      (node (ref "J1") (pin "C1") (pinfunction "C1_C1") (pintype "bidirectional"))
      (node (ref "J1") (pin "C10") (pinfunction "C10_C10") (pintype "bidirectional"))
      (node (ref "J1") (pin "C13") (pinfunction "C13_C13") (pintype "bidirectional"))
      (node (ref "J1") (pin "C14") (pinfunction "C14_C14") (pintype "bidirectional"))
      (node (ref "J1") (pin "C2") (pinfunction "C2_C2") (pintype "bidirectional"))
      (node (ref "J1") (pin "C25") (pinfunction "C25_C25") (pintype "bidirectional"))
      (node (ref "J1") (pin "C26") (pinfunction "C26_C26") (pintype "bidirectional"))
      (node (ref "J1") (pin "C29") (pinfunction "C29_C29") (pintype "bidirectional"))
      (node (ref "J1") (pin "C30") (pinfunction "C30_C30") (pintype "bidirectional"))
      (node (ref "J1") (pin "C5") (pinfunction "C5_C5") (pintype "bidirectional"))
      (node (ref "J1") (pin "C6") (pinfunction "C6_C6") (pintype "bidirectional"))
      (node (ref "J1") (pin "C9") (pinfunction "C9_C9") (pintype "bidirectional"))
      (node (ref "J1") (pin "CG1") (pinfunction "CG1_CG1") (pintype "power_in"))
      (node (ref "J1") (pin "CG10") (pinfunction "CG10_CG10") (pintype "power_in"))
      (node (ref "J1") (pin "CG11") (pinfunction "CG11_CG11") (pintype "power_in"))
      (node (ref "J1") (pin "CG12") (pinfunction "CG12_CG12") (pintype "power_in"))
      (node (ref "J1") (pin "CG13") (pinfunction "CG13_CG13") (pintype "power_in"))
      (node (ref "J1") (pin "CG14") (pinfunction "CG14_CG14") (pintype "power_in"))
      (node (ref "J1") (pin "CG15") (pinfunction "CG15_CG15") (pintype "power_in"))
      (node (ref "J1") (pin "CG16") (pinfunction "CG16_CG16") (pintype "power_in"))
      (node (ref "J1") (pin "CG17") (pinfunction "CG17_CG17") (pintype "power_in"))
      (node (ref "J1") (pin "CG18") (pinfunction "CG18_CG18") (pintype "power_in"))
      (node (ref "J1") (pin "CG19") (pinfunction "CG19_CG19") (pintype "power_in"))
      (node (ref "J1") (pin "CG2") (pinfunction "CG2_CG2") (pintype "power_in"))
      (node (ref "J1") (pin "CG20") (pinfunction "CG20_CG20") (pintype "power_in"))
      (node (ref "J1") (pin "CG3") (pinfunction "CG3_CG3") (pintype "power_in"))
      (node (ref "J1") (pin "CG4") (pinfunction "CG4_CG4") (pintype "power_in"))
      (node (ref "J1") (pin "CG5") (pinfunction "CG5_CG5") (pintype "power_in"))
      (node (ref "J1") (pin "CG6") (pinfunction "CG6_CG6") (pintype "power_in"))
      (node (ref "J1") (pin "CG7") (pinfunction "CG7_CG7") (pintype "power_in"))
      (node (ref "J1") (pin "CG8") (pinfunction "CG8_CG8") (pintype "power_in"))
      (node (ref "J1") (pin "CG9") (pinfunction "CG9_CG9") (pintype "power_in"))
      (node (ref "J1") (pin "CGND") (pinfunction "CGND_CGND") (pintype "power_in"))
      (node (ref "J1") (pin "D1") (pinfunction "D1_D1") (pintype "bidirectional"))
      (node (ref "J1") (pin "D10") (pinfunction "D10_D10") (pintype "bidirectional"))
      (node (ref "J1") (pin "D13") (pinfunction "D13_D13") (pintype "bidirectional"))
      (node (ref "J1") (pin "D14") (pinfunction "D14_D14") (pintype "bidirectional"))
      (node (ref "J1") (pin "D2") (pinfunction "D2_D2") (pintype "bidirectional"))
      (node (ref "J1") (pin "D25") (pinfunction "D25_D25") (pintype "bidirectional"))
      (node (ref "J1") (pin "D26") (pinfunction "D26_D26") (pintype "bidirectional"))
      (node (ref "J1") (pin "D29") (pinfunction "D29_D29") (pintype "bidirectional"))
      (node (ref "J1") (pin "D30") (pinfunction "D30_D30") (pintype "bidirectional"))
      (node (ref "J1") (pin "D5") (pinfunction "D5_D5") (pintype "bidirectional"))
      (node (ref "J1") (pin "D6") (pinfunction "D6_D6") (pintype "bidirectional"))
      (node (ref "J1") (pin "D9") (pinfunction "D9_D9") (pintype "bidirectional"))
      (node (ref "J1") (pin "DG1") (pinfunction "DG1_DG1") (pintype "power_in"))
      (node (ref "J1") (pin "DG10") (pinfunction "DG10_DG10") (pintype "power_in"))
      (node (ref "J1") (pin "DG11") (pinfunction "DG11_DG11") (pintype "power_in"))
      (node (ref "J1") (pin "DG12") (pinfunction "DG12_DG12") (pintype "power_in"))
      (node (ref "J1") (pin "DG13") (pinfunction "DG13_DG13") (pintype "power_in"))
      (node (ref "J1") (pin "DG14") (pinfunction "DG14_DG14") (pintype "power_in"))
      (node (ref "J1") (pin "DG15") (pinfunction "DG15_DG15") (pintype "power_in"))
      (node (ref "J1") (pin "DG16") (pinfunction "DG16_DG16") (pintype "power_in"))
      (node (ref "J1") (pin "DG17") (pinfunction "DG17_DG17") (pintype "power_in"))
      (node (ref "J1") (pin "DG18") (pinfunction "DG18_DG18") (pintype "power_in"))
      (node (ref "J1") (pin "DG19") (pinfunction "DG19_DG19") (pintype "power_in"))
      (node (ref "J1") (pin "DG2") (pinfunction "DG2_DG2") (pintype "power_in"))
      (node (ref "J1") (pin "DG20") (pinfunction "DG20_DG20") (pintype "power_in"))
      (node (ref "J1") (pin "DG3") (pinfunction "DG3_DG3") (pintype "power_in"))
      (node (ref "J1") (pin "DG4") (pinfunction "DG4_DG4") (pintype "power_in"))
      (node (ref "J1") (pin "DG5") (pinfunction "DG5_DG5") (pintype "power_in"))
      (node (ref "J1") (pin "DG6") (pinfunction "DG6_DG6") (pintype "power_in"))
      (node (ref "J1") (pin "DG7") (pinfunction "DG7_DG7") (pintype "power_in"))
      (node (ref "J1") (pin "DG8") (pinfunction "DG8_DG8") (pintype "power_in"))
      (node (ref "J1") (pin "DG9") (pinfunction "DG9_DG9") (pintype "power_in"))
      (node (ref "J1") (pin "DGND") (pinfunction "DGND_DGND") (pintype "power_in"))
      (node (ref "P6") (pin "11") (pinfunction "11_11") (pintype "passive"))
      (node (ref "P6") (pin "12") (pinfunction "12_12") (pintype "passive"))
      (node (ref "P6") (pin "3") (pinfunction "3_3") (pintype "passive"))
      (node (ref "P6") (pin "4") (pinfunction "4_4") (pintype "passive"))
      (node (ref "P6") (pin "7") (pinfunction "7_7") (pintype "passive"))
      (node (ref "P6") (pin "8") (pinfunction "8_8") (pintype "passive"))
      (node (ref "R10") (pin "1") (pinfunction "1_1") (pintype "passive"))
      (node (ref "R11") (pin "1") (pinfunction "1_1") (pintype "passive"))
      (node (ref "R3") (pin "1") (pinfunction "1_1") (pintype "passive"))
      (node (ref "R46") (pin "1") (pinfunction "1_1") (pintype "passive"))
      (node (ref "R6") (pin "1") (pinfunction "1_1") (pintype "passive"))
      (node (ref "R68") (pin "1") (pinfunction "1_1") (pintype "passive"))
      (node (ref "R9") (pin "1") (pinfunction "1_1") (pintype "passive"))
      (node (ref "U10") (pin "12") (pinfunction "GND_12") (pintype "power_in"))
      (node (ref "U10") (pin "21") (pinfunction "TH_GND_21") (pintype "power_in"))
      (node (ref "U3") (pin "12") (pinfunction "GND_12") (pintype "power_in"))
      (node (ref "U3") (pin "21") (pinfunction "TH_GND_21") (pintype "power_in"))
      (node (ref "U4") (pin "12") (pinfunction "GND_12") (pintype "power_in"))
      (node (ref "U4") (pin "21") (pinfunction "TH_GND_21") (pintype "power_in"))
      (node (ref "U9") (pin "12") (pinfunction "GND_12") (pintype "power_in"))
      (node (ref "U9") (pin "21") (pinfunction "TH_GND_21") (pintype "power_in"))
    )
    (net (code "89") (name "Net-(U3-FB)") (class "Default")
      (node (ref "R2") (pin "1") (pinfunction "1_1") (pintype "passive"))
      (node (ref "R3") (pin "2") (pinfunction "2_2") (pintype "passive"))
      (node (ref "U3") (pin "16") (pinfunction "FB_16") (pintype "input"))
    )
    (net (code "90") (name "Net-(U3-PG)") (class "Default")
      (node (ref "R1") (pin "1") (pinfunction "1_1") (pintype "passive"))
      (node (ref "TP1") (pin "1") (pinfunction "1_1") (pintype "passive"))
      (node (ref "U3") (pin "9") (pinfunction "PG_9") (pintype "output"))
    )
    (net (code "91") (name "Net-(U3-SS)") (class "Default")
      (node (ref "C38") (pin "2") (pinfunction "2_2") (pintype "passive"))
      (node (ref "U3") (pin "15") (pinfunction "SS_15") (pintype "passive"))
    )
    (net (code "92") (name "Net-(U4-FB)") (class "Default")
      (node (ref "R5") (pin "1") (pinfunction "1_1") (pintype "passive"))
      (node (ref "R6") (pin "2") (pinfunction "2_2") (pintype "passive"))
      (node (ref "U4") (pin "16") (pinfunction "FB_16") (pintype "input"))
    )
    (net (code "93") (name "Net-(U4-PG)") (class "Default")
      (node (ref "R4") (pin "1") (pinfunction "1_1") (pintype "passive"))
      (node (ref "TP2") (pin "1") (pinfunction "1_1") (pintype "passive"))
      (node (ref "U4") (pin "9") (pinfunction "PG_9") (pintype "output"))
    )
    (net (code "94") (name "Net-(U4-SS)") (class "Default")
      (node (ref "C44") (pin "2") (pinfunction "2_2") (pintype "passive"))
      (node (ref "U4") (pin "15") (pinfunction "SS_15") (pintype "passive"))
    )
    (net (code "95") (name "Net-(U9-FB)") (class "Default")
      (node (ref "R45") (pin "1") (pinfunction "1_1") (pintype "passive"))
      (node (ref "R46") (pin "2") (pinfunction "2_2") (pintype "passive"))
      (node (ref "U9") (pin "16") (pinfunction "FB_16") (pintype "input"))
    )
    (net (code "96") (name "Net-(U9-PG)") (class "Default")
      (node (ref "R44") (pin "1") (pinfunction "1_1") (pintype "passive"))
      (node (ref "TP4") (pin "1") (pinfunction "1_1") (pintype "passive"))
      (node (ref "U9") (pin "9") (pinfunction "PG_9") (pintype "output"))
    )
    (net (code "97") (name "Net-(U9-SS)") (class "Default")
      (node (ref "C128") (pin "2") (pinfunction "2_2") (pintype "passive"))
      (node (ref "U9") (pin "15") (pinfunction "SS_15") (pintype "passive"))
    )
    (net (code "98") (name "Net-(U10-FB)") (class "Default")
      (node (ref "R67") (pin "1") (pinfunction "1_1") (pintype "passive"))
      (node (ref "R68") (pin "2") (pinfunction "2_2") (pintype "passive"))
      (node (ref "U10") (pin "16") (pinfunction "FB_16") (pintype "input"))
    )
    (net (code "99") (name "Net-(U10-PG)") (class "Default")
      (node (ref "R66") (pin "1") (pinfunction "1_1") (pintype "passive"))
      (node (ref "TP5") (pin "1") (pinfunction "1_1") (pintype "passive"))
      (node (ref "U10") (pin "9") (pinfunction "PG_9") (pintype "output"))
    )
    (net (code "100") (name "Net-(U10-SS)") (class "Default")
      (node (ref "C147") (pin "2") (pinfunction "2_2") (pintype "passive"))
      (node (ref "U10") (pin "15") (pinfunction "SS_15") (pintype "passive"))
    )
    (net (code "101") (name "unconnected-(J1-PadC22)") (class "Default")
      (node (ref "J1") (pin "C22") (pinfunction "C22_C22") (pintype "bidirectional+no_connect"))
    )
    (net (code "102") (name "unconnected-(J1-PadC23)") (class "Default")
      (node (ref "J1") (pin "C23") (pinfunction "C23_C23") (pintype "bidirectional+no_connect"))
    )
    (net (code "103") (name "unconnected-(J1-PadC24)") (class "Default")
      (node (ref "J1") (pin "C24") (pinfunction "C24_C24") (pintype "bidirectional+no_connect"))
    )
    (net (code "104") (name "unconnected-(J1-PadD17)") (class "Default")
      (node (ref "J1") (pin "D17") (pinfunction "D17_D17") (pintype "bidirectional"))
    )
    (net (code "105") (name "unconnected-(J1-PadD18)") (class "Default")
      (node (ref "J1") (pin "D18") (pinfunction "D18_D18") (pintype "bidirectional+no_connect"))
    )
    (net (code "106") (name "unconnected-(J1-PadD19)") (class "Default")
      (node (ref "J1") (pin "D19") (pinfunction "D19_D19") (pintype "bidirectional+no_connect"))
    )
    (net (code "107") (name "unconnected-(J1-PadD20)") (class "Default")
      (node (ref "J1") (pin "D20") (pinfunction "D20_D20") (pintype "bidirectional+no_connect"))
    )
    (net (code "108") (name "unconnected-(J1-PadD21)") (class "Default")
      (node (ref "J1") (pin "D21") (pinfunction "D21_D21") (pintype "bidirectional+no_connect"))
    )
    (net (code "109") (name "unconnected-(J1-PadD22)") (class "Default")
      (node (ref "J1") (pin "D22") (pinfunction "D22_D22") (pintype "bidirectional+no_connect"))
    )
    (net (code "110") (name "unconnected-(J1-PadD23)") (class "Default")
      (node (ref "J1") (pin "D23") (pinfunction "D23_D23") (pintype "bidirectional+no_connect"))
    )
    (net (code "111") (name "unconnected-(J1-PadD24)") (class "Default")
      (node (ref "J1") (pin "D24") (pinfunction "D24_D24") (pintype "bidirectional+no_connect"))
    )
    (net (code "112") (name "unconnected-(U3-NC-Pad2)") (class "Default")
      (node (ref "U3") (pin "2") (pinfunction "NC_2") (pintype "passive+no_connect"))
    )
    (net (code "113") (name "unconnected-(U3-NC-Pad3)") (class "Default")
      (node (ref "U3") (pin "3") (pinfunction "NC_3") (pintype "passive+no_connect"))
    )
    (net (code "114") (name "unconnected-(U3-NC-Pad4)") (class "Default")
      (node (ref "U3") (pin "4") (pinfunction "NC_4") (pintype "passive+no_connect"))
    )
    (net (code "115") (name "unconnected-(U3-NC-Pad13)") (class "Default")
      (node (ref "U3") (pin "13") (pinfunction "NC_13") (pintype "passive+no_connect"))
    )
    (net (code "116") (name "unconnected-(U3-NC-Pad14)") (class "Default")
      (node (ref "U3") (pin "14") (pinfunction "NC_14") (pintype "passive+no_connect"))
    )
    (net (code "117") (name "unconnected-(U3-NC-Pad17)") (class "Default")
      (node (ref "U3") (pin "17") (pinfunction "NC_17") (pintype "passive+no_connect"))
    )
    (net (code "118") (name "unconnected-(U4-NC-Pad2)") (class "Default")
      (node (ref "U4") (pin "2") (pinfunction "NC_2") (pintype "passive+no_connect"))
    )
    (net (code "119") (name "unconnected-(U4-NC-Pad3)") (class "Default")
      (node (ref "U4") (pin "3") (pinfunction "NC_3") (pintype "passive+no_connect"))
    )
    (net (code "120") (name "unconnected-(U4-NC-Pad4)") (class "Default")
      (node (ref "U4") (pin "4") (pinfunction "NC_4") (pintype "passive+no_connect"))
    )
    (net (code "121") (name "unconnected-(U4-NC-Pad13)") (class "Default")
      (node (ref "U4") (pin "13") (pinfunction "NC_13") (pintype "passive+no_connect"))
    )
    (net (code "122") (name "unconnected-(U4-NC-Pad14)") (class "Default")
      (node (ref "U4") (pin "14") (pinfunction "NC_14") (pintype "passive+no_connect"))
    )
    (net (code "123") (name "unconnected-(U4-NC-Pad17)") (class "Default")
      (node (ref "U4") (pin "17") (pinfunction "NC_17") (pintype "passive+no_connect"))
    )
    (net (code "124") (name "unconnected-(U9-NC-Pad2)") (class "Default")
      (node (ref "U9") (pin "2") (pinfunction "NC_2") (pintype "passive+no_connect"))
    )
    (net (code "125") (name "unconnected-(U9-NC-Pad3)") (class "Default")
      (node (ref "U9") (pin "3") (pinfunction "NC_3") (pintype "passive+no_connect"))
    )
    (net (code "126") (name "unconnected-(U9-NC-Pad4)") (class "Default")
      (node (ref "U9") (pin "4") (pinfunction "NC_4") (pintype "passive+no_connect"))
    )
    (net (code "127") (name "unconnected-(U9-NC-Pad13)") (class "Default")
      (node (ref "U9") (pin "13") (pinfunction "NC_13") (pintype "passive+no_connect"))
    )
    (net (code "128") (name "unconnected-(U9-NC-Pad14)") (class "Default")
      (node (ref "U9") (pin "14") (pinfunction "NC_14") (pintype "passive+no_connect"))
    )
    (net (code "129") (name "unconnected-(U9-NC-Pad17)") (class "Default")
      (node (ref "U9") (pin "17") (pinfunction "NC_17") (pintype "passive+no_connect"))
    )
    (net (code "130") (name "unconnected-(U10-NC-Pad2)") (class "Default")
      (node (ref "U10") (pin "2") (pinfunction "NC_2") (pintype "passive+no_connect"))
    )
    (net (code "131") (name "unconnected-(U10-NC-Pad3)") (class "Default")
      (node (ref "U10") (pin "3") (pinfunction "NC_3") (pintype "passive+no_connect"))
    )
    (net (code "132") (name "unconnected-(U10-NC-Pad4)") (class "Default")
      (node (ref "U10") (pin "4") (pinfunction "NC_4") (pintype "passive+no_connect"))
    )
    (net (code "133") (name "unconnected-(U10-NC-Pad13)") (class "Default")
      (node (ref "U10") (pin "13") (pinfunction "NC_13") (pintype "passive+no_connect"))
    )
    (net (code "134") (name "unconnected-(U10-NC-Pad14)") (class "Default")
      (node (ref "U10") (pin "14") (pinfunction "NC_14") (pintype "passive+no_connect"))
    )
    (net (code "135") (name "unconnected-(U10-NC-Pad17)") (class "Default")
      (node (ref "U10") (pin "17") (pinfunction "NC_17") (pintype "passive+no_connect"))
    )
  )
)
